# PATHS_1_1.net
KiCad netlist of a schematic drawn in EAGLE
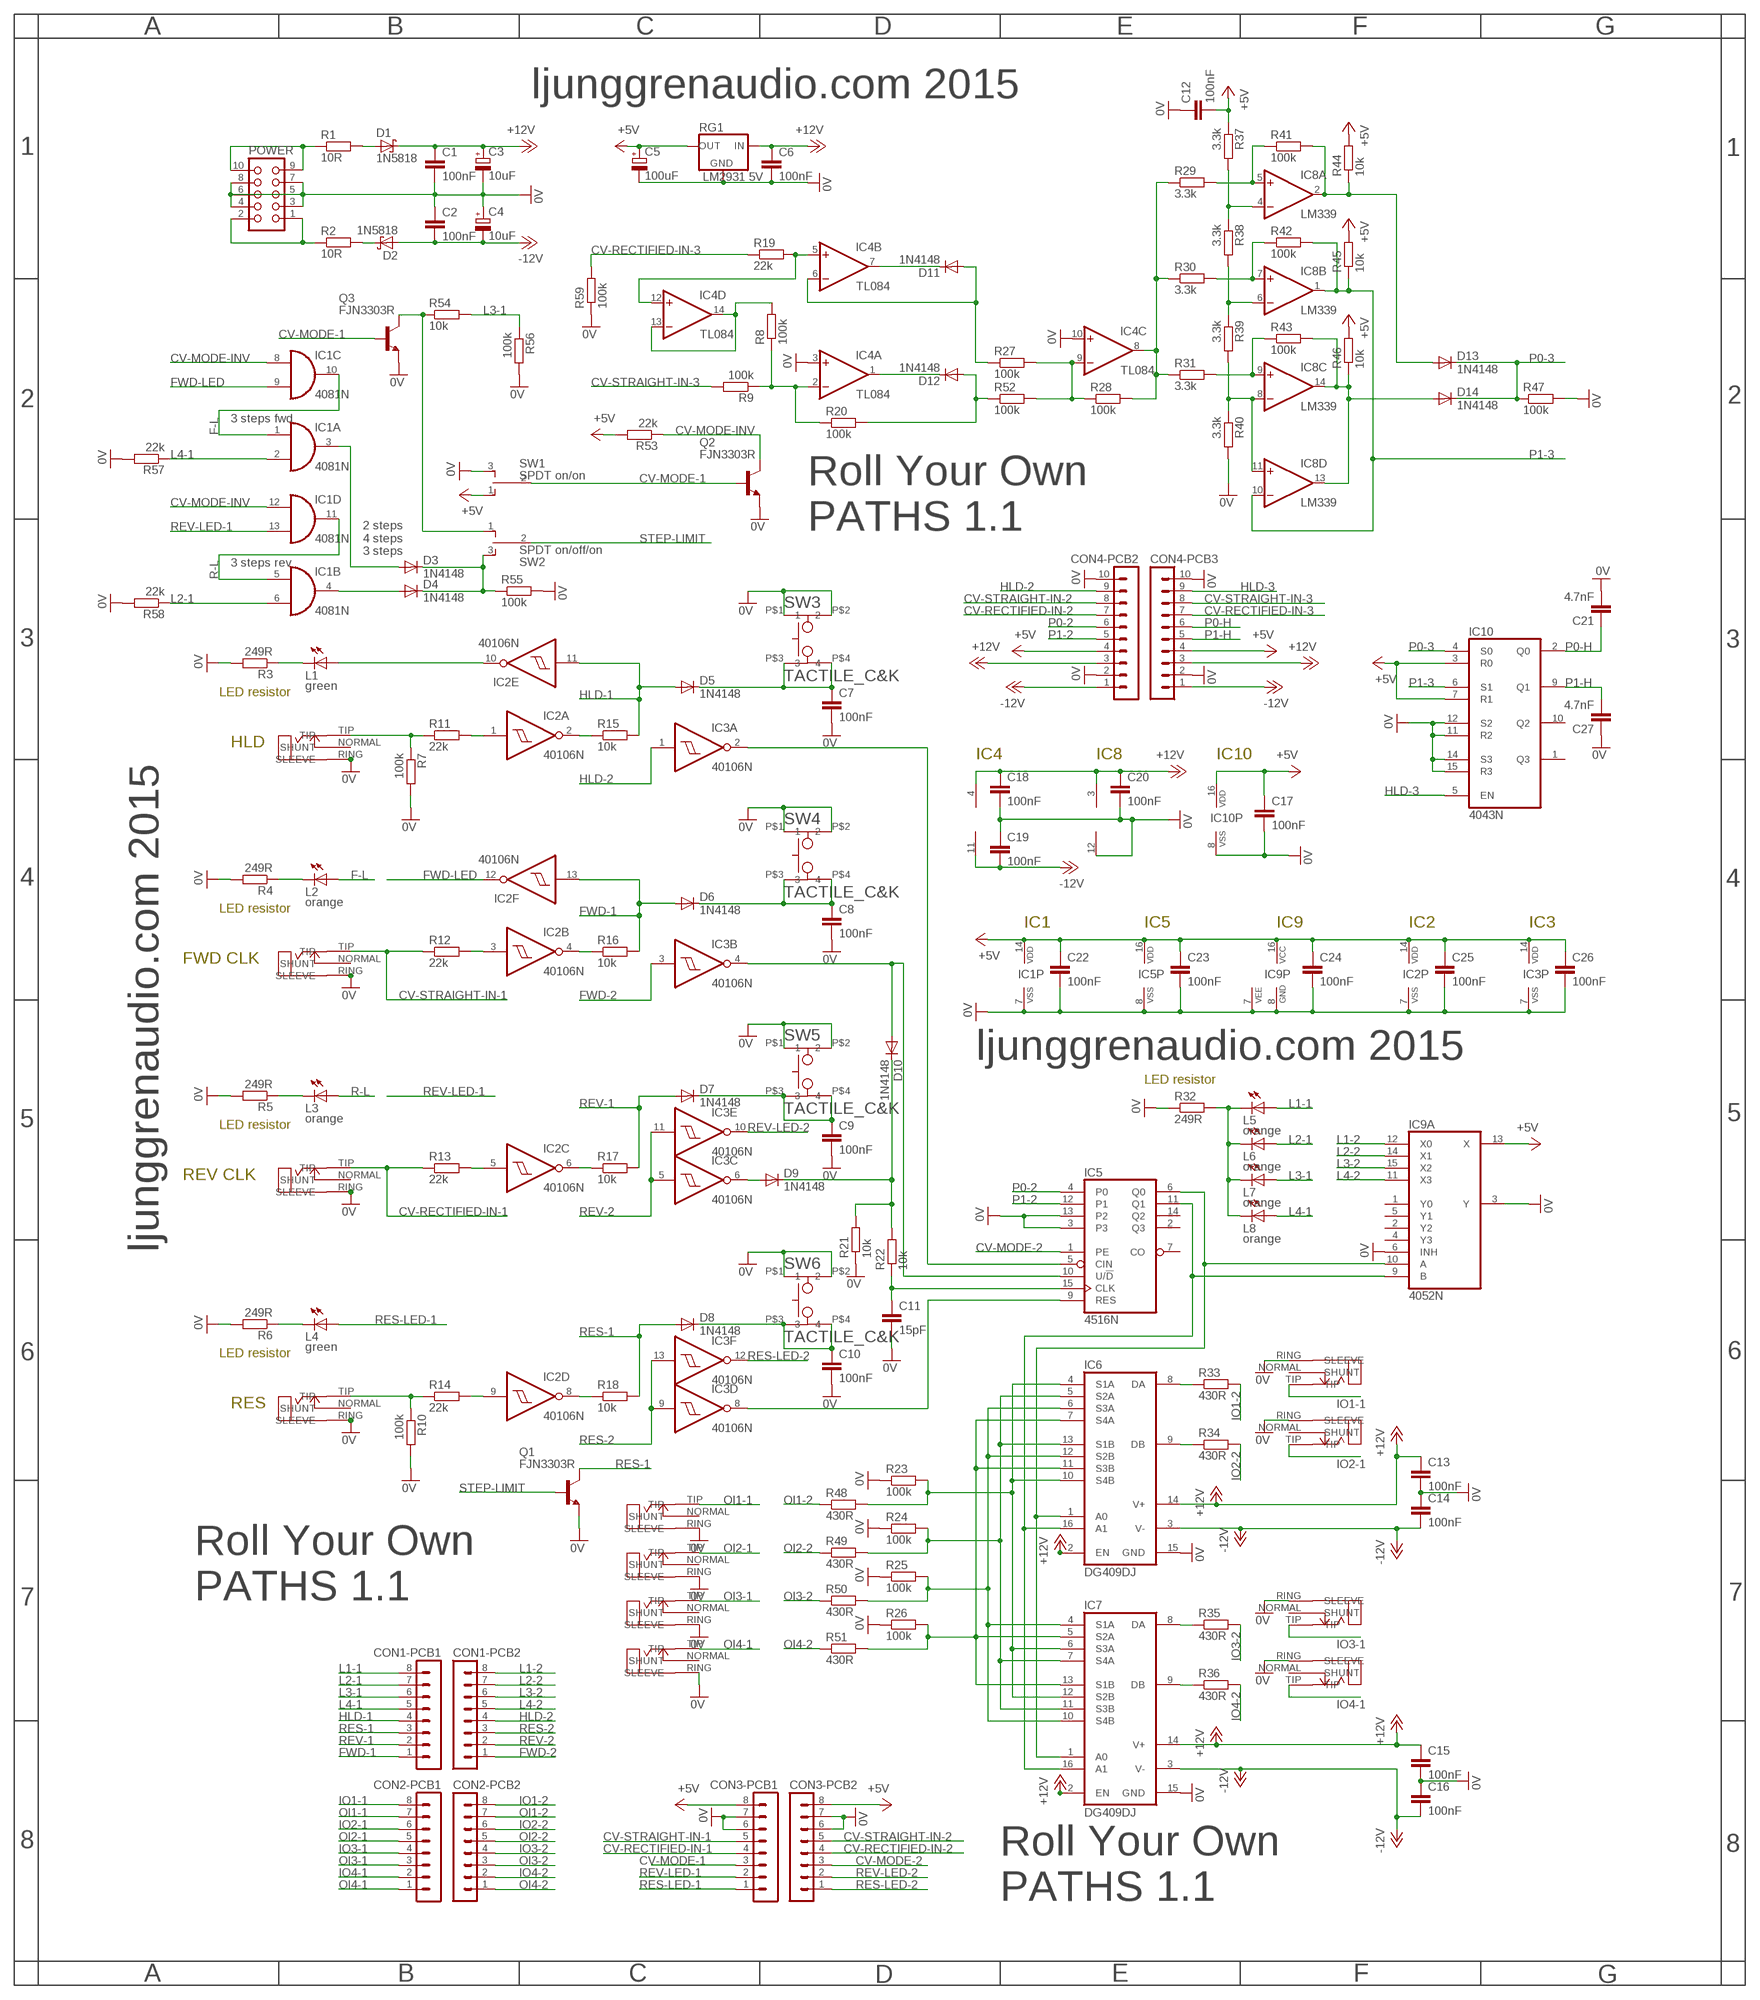
[diagram p0: schematic, sheet 1]

(export (version "E")
  (design (tool "Eeschema 10.0.6"))
  (components
    (comp (ref "C1")
      (value "100nF")
      (footprint "eagle-import:C025-024X044")
      (libsource (lib "eagle-import") (part "C-EU025-024X044"))
    )
    (comp (ref "C2")
      (value "100nF")
      (footprint "eagle-import:C025-024X044")
      (libsource (lib "eagle-import") (part "C-EU025-024X044"))
    )
    (comp (ref "C3")
      (value "10uF")
      (footprint "eagle-import:E2-5")
      (libsource (lib "eagle-import") (part "CPOL-EUE2-5"))
    )
    (comp (ref "C4")
      (value "10uF")
      (footprint "eagle-import:E2-5")
      (libsource (lib "eagle-import") (part "CPOL-EUE2-5"))
    )
    (comp (ref "C5")
      (value "100uF")
      (footprint "eagle-import:E2,5-6")
      (libsource (lib "eagle-import") (part "CPOL-EUE2.5-6"))
    )
    (comp (ref "C6")
      (value "100nF")
      (footprint "eagle-import:C025-024X044")
      (libsource (lib "eagle-import") (part "C-EU025-024X044"))
    )
    (comp (ref "C7")
      (value "100nF")
      (footprint "eagle-import:C025-024X044")
      (libsource (lib "eagle-import") (part "C-EU025-024X044"))
    )
    (comp (ref "C8")
      (value "100nF")
      (footprint "eagle-import:C025-024X044")
      (libsource (lib "eagle-import") (part "C-EU025-024X044"))
    )
    (comp (ref "C9")
      (value "100nF")
      (footprint "eagle-import:C025-024X044")
      (libsource (lib "eagle-import") (part "C-EU025-024X044"))
    )
    (comp (ref "C10")
      (value "100nF")
      (footprint "eagle-import:C025-024X044")
      (libsource (lib "eagle-import") (part "C-EU025-024X044"))
    )
    (comp (ref "C11")
      (value "15pF")
      (footprint "eagle-import:C025-024X044")
      (libsource (lib "eagle-import") (part "C-EU025-024X044"))
    )
    (comp (ref "C12")
      (value "100nF")
      (footprint "eagle-import:C025-024X044")
      (libsource (lib "eagle-import") (part "C-EU025-024X044"))
    )
    (comp (ref "C13")
      (value "100nF")
      (footprint "eagle-import:C025-024X044")
      (libsource (lib "eagle-import") (part "C-EU025-024X044"))
    )
    (comp (ref "C14")
      (value "100nF")
      (footprint "eagle-import:C025-024X044")
      (libsource (lib "eagle-import") (part "C-EU025-024X044"))
    )
    (comp (ref "C15")
      (value "100nF")
      (footprint "eagle-import:C025-024X044")
      (libsource (lib "eagle-import") (part "C-EU025-024X044"))
    )
    (comp (ref "C16")
      (value "100nF")
      (footprint "eagle-import:C025-024X044")
      (libsource (lib "eagle-import") (part "C-EU025-024X044"))
    )
    (comp (ref "C17")
      (value "100nF")
      (footprint "eagle-import:C025-024X044")
      (libsource (lib "eagle-import") (part "C-EU025-024X044"))
    )
    (comp (ref "C18")
      (value "100nF")
      (footprint "eagle-import:C025-024X044")
      (libsource (lib "eagle-import") (part "C-EU025-024X044"))
    )
    (comp (ref "C19")
      (value "100nF")
      (footprint "eagle-import:C025-024X044")
      (libsource (lib "eagle-import") (part "C-EU025-024X044"))
    )
    (comp (ref "C20")
      (value "100nF")
      (footprint "eagle-import:C025-024X044")
      (libsource (lib "eagle-import") (part "C-EU025-024X044"))
    )
    (comp (ref "C21")
      (value "4.7nF")
      (footprint "eagle-import:C025-024X044")
      (libsource (lib "eagle-import") (part "C-EU025-024X044"))
    )
    (comp (ref "C22")
      (value "100nF")
      (footprint "eagle-import:C025-024X044")
      (libsource (lib "eagle-import") (part "C-EU025-024X044"))
    )
    (comp (ref "C23")
      (value "100nF")
      (footprint "eagle-import:C025-024X044")
      (libsource (lib "eagle-import") (part "C-EU025-024X044"))
    )
    (comp (ref "C24")
      (value "100nF")
      (footprint "eagle-import:C025-024X044")
      (libsource (lib "eagle-import") (part "C-EU025-024X044"))
    )
    (comp (ref "C25")
      (value "100nF")
      (footprint "eagle-import:C025-024X044")
      (libsource (lib "eagle-import") (part "C-EU025-024X044"))
    )
    (comp (ref "C26")
      (value "100nF")
      (footprint "eagle-import:C025-024X044")
      (libsource (lib "eagle-import") (part "C-EU025-024X044"))
    )
    (comp (ref "C27")
      (value "4.7nF")
      (footprint "eagle-import:C025-024X044")
      (libsource (lib "eagle-import") (part "C-EU025-024X044"))
    )
    (comp (ref "CON1-PCB1")
      (value "MA08-1")
      (footprint "eagle-import:MA08-1")
      (libsource (lib "eagle-import") (part "MA08-1"))
    )
    (comp (ref "CON1-PCB2")
      (value "MA08-1")
      (footprint "eagle-import:MA08-1")
      (libsource (lib "eagle-import") (part "MA08-1"))
    )
    (comp (ref "CON2-PCB1")
      (value "MA08-1")
      (footprint "eagle-import:MA08-1")
      (libsource (lib "eagle-import") (part "MA08-1"))
    )
    (comp (ref "CON2-PCB2")
      (value "MA08-1")
      (footprint "eagle-import:MA08-1")
      (libsource (lib "eagle-import") (part "MA08-1"))
    )
    (comp (ref "CON3-PCB1")
      (value "MA08-1")
      (footprint "eagle-import:MA08-1")
      (libsource (lib "eagle-import") (part "MA08-1"))
    )
    (comp (ref "CON3-PCB2")
      (value "MA08-1")
      (footprint "eagle-import:MA08-1")
      (libsource (lib "eagle-import") (part "MA08-1"))
    )
    (comp (ref "CON4-PCB2")
      (value "MA10-1")
      (footprint "eagle-import:MA10-1")
      (libsource (lib "eagle-import") (part "MA10-1"))
    )
    (comp (ref "CON4-PCB3")
      (value "MA10-1")
      (footprint "eagle-import:MA10-1")
      (libsource (lib "eagle-import") (part "MA10-1"))
    )
    (comp (ref "D1")
      (value "1N5818")
      (footprint "eagle-import:DO41-7")
      (libsource (lib "eagle-import") (part "SB130DO-204AL"))
    )
    (comp (ref "D2")
      (value "1N5818")
      (footprint "eagle-import:DO41-7")
      (libsource (lib "eagle-import") (part "SB130DO-204AL"))
    )
    (comp (ref "D3")
      (value "1N4148")
      (footprint "eagle-import:DO35-6")
      (libsource (lib "eagle-import") (part "1N4148DO35-6"))
    )
    (comp (ref "D4")
      (value "1N4148")
      (footprint "eagle-import:DO35-6")
      (libsource (lib "eagle-import") (part "1N4148DO35-6"))
    )
    (comp (ref "D5")
      (value "1N4148")
      (footprint "eagle-import:DO35-6")
      (libsource (lib "eagle-import") (part "1N4148DO35-6"))
    )
    (comp (ref "D6")
      (value "1N4148")
      (footprint "eagle-import:DO35-6")
      (libsource (lib "eagle-import") (part "1N4148DO35-6"))
    )
    (comp (ref "D7")
      (value "1N4148")
      (footprint "eagle-import:DO35-6")
      (libsource (lib "eagle-import") (part "1N4148DO35-6"))
    )
    (comp (ref "D8")
      (value "1N4148")
      (footprint "eagle-import:DO35-6")
      (libsource (lib "eagle-import") (part "1N4148DO35-6"))
    )
    (comp (ref "D9")
      (value "1N4148")
      (footprint "eagle-import:DO35-6")
      (libsource (lib "eagle-import") (part "1N4148DO35-6"))
    )
    (comp (ref "D10")
      (value "1N4148")
      (footprint "eagle-import:DO35-6")
      (libsource (lib "eagle-import") (part "1N4148DO35-6"))
    )
    (comp (ref "D11")
      (value "1N4148")
      (footprint "eagle-import:DO35-6")
      (libsource (lib "eagle-import") (part "1N4148DO35-6"))
    )
    (comp (ref "D12")
      (value "1N4148")
      (footprint "eagle-import:DO35-6")
      (libsource (lib "eagle-import") (part "1N4148DO35-6"))
    )
    (comp (ref "D13")
      (value "1N4148")
      (footprint "eagle-import:DO35-6")
      (libsource (lib "eagle-import") (part "1N4148DO35-6"))
    )
    (comp (ref "D14")
      (value "1N4148")
      (footprint "eagle-import:DO35-6")
      (libsource (lib "eagle-import") (part "1N4148DO35-6"))
    )
    (comp (ref "FWD")
      (value "ERTHENVAR_3.5MM_JACKINLINE2")
      (footprint "eagle-import:THONKICON-TWISTED")
      (libsource (lib "eagle-import") (part "ERTHENVAR_3.5MM_JACKINLINE2"))
    )
    (comp (ref "HLD")
      (value "ERTHENVAR_3.5MM_JACKINLINE2")
      (footprint "eagle-import:THONKICON-TWISTED")
      (libsource (lib "eagle-import") (part "ERTHENVAR_3.5MM_JACKINLINE2"))
    )
    (comp (ref "I/O1")
      (value "ERTHENVAR_3.5MM_JACKINLINE2")
      (footprint "eagle-import:THONKICON-TWISTED")
      (libsource (lib "eagle-import") (part "ERTHENVAR_3.5MM_JACKINLINE2"))
    )
    (comp (ref "I/O2")
      (value "ERTHENVAR_3.5MM_JACKINLINE2")
      (footprint "eagle-import:THONKICON-TWISTED")
      (libsource (lib "eagle-import") (part "ERTHENVAR_3.5MM_JACKINLINE2"))
    )
    (comp (ref "I/O3")
      (value "ERTHENVAR_3.5MM_JACKINLINE2")
      (footprint "eagle-import:THONKICON-TWISTED")
      (libsource (lib "eagle-import") (part "ERTHENVAR_3.5MM_JACKINLINE2"))
    )
    (comp (ref "I/O4")
      (value "ERTHENVAR_3.5MM_JACKINLINE2")
      (footprint "eagle-import:THONKICON-TWISTED")
      (libsource (lib "eagle-import") (part "ERTHENVAR_3.5MM_JACKINLINE2"))
    )
    (comp (ref "IC1")
      (value "4081N")
      (footprint "eagle-import:DIL14")
      (libsource (lib "eagle-import") (part "4081N"))
    )
    (comp (ref "IC2")
      (value "40106N")
      (footprint "eagle-import:DIL14")
      (libsource (lib "eagle-import") (part "40106N"))
    )
    (comp (ref "IC3")
      (value "40106N")
      (footprint "eagle-import:DIL14")
      (libsource (lib "eagle-import") (part "40106N"))
    )
    (comp (ref "IC4")
      (value "TL084")
      (footprint "eagle-import:DIL14")
      (libsource (lib "eagle-import") (part "TL074P"))
    )
    (comp (ref "IC5")
      (value "4516N")
      (footprint "eagle-import:DIL16")
      (libsource (lib "eagle-import") (part "4516N"))
    )
    (comp (ref "IC6")
      (value "DG409DJ")
      (footprint "eagle-import:DIL16")
      (fields (field (name "MF") "INTERSIL"))
      (libsource (lib "eagle-import") (part "DG409DJ"))
    )
    (comp (ref "IC7")
      (value "DG409DJ")
      (footprint "eagle-import:DIL16")
      (fields (field (name "MF") "INTERSIL"))
      (libsource (lib "eagle-import") (part "DG409DJ"))
    )
    (comp (ref "IC8")
      (value "LM339")
      (footprint "eagle-import:DIL14")
      (libsource (lib "eagle-import") (part "LM2901N"))
    )
    (comp (ref "IC9")
      (value "4052N")
      (footprint "eagle-import:DIL16")
      (libsource (lib "eagle-import") (part "4052N"))
    )
    (comp (ref "IC10")
      (value "4043N")
      (footprint "eagle-import:DIL16")
      (libsource (lib "eagle-import") (part "4043N"))
    )
    (comp (ref "L1")
      (value "green")
      (footprint "eagle-import:LED3MM")
      (libsource (lib "eagle-import") (part "LED3MM"))
    )
    (comp (ref "L2")
      (value "orange")
      (footprint "eagle-import:LED3MM")
      (libsource (lib "eagle-import") (part "LED3MM"))
    )
    (comp (ref "L3")
      (value "orange")
      (footprint "eagle-import:LED3MM")
      (libsource (lib "eagle-import") (part "LED3MM"))
    )
    (comp (ref "L4")
      (value "green")
      (footprint "eagle-import:LED3MM")
      (libsource (lib "eagle-import") (part "LED3MM"))
    )
    (comp (ref "L5")
      (value "orange")
      (footprint "eagle-import:LED3MM")
      (libsource (lib "eagle-import") (part "LED3MM"))
    )
    (comp (ref "L6")
      (value "orange")
      (footprint "eagle-import:LED3MM")
      (libsource (lib "eagle-import") (part "LED3MM"))
    )
    (comp (ref "L7")
      (value "orange")
      (footprint "eagle-import:LED3MM")
      (libsource (lib "eagle-import") (part "LED3MM"))
    )
    (comp (ref "L8")
      (value "orange")
      (footprint "eagle-import:LED3MM")
      (libsource (lib "eagle-import") (part "LED3MM"))
    )
    (comp (ref "O/I1")
      (value "ERTHENVAR_3.5MM_JACKINLINE2")
      (footprint "eagle-import:THONKICON-TWISTED")
      (libsource (lib "eagle-import") (part "ERTHENVAR_3.5MM_JACKINLINE2"))
    )
    (comp (ref "O/I2")
      (value "ERTHENVAR_3.5MM_JACKINLINE2")
      (footprint "eagle-import:THONKICON-TWISTED")
      (libsource (lib "eagle-import") (part "ERTHENVAR_3.5MM_JACKINLINE2"))
    )
    (comp (ref "O/I3")
      (value "ERTHENVAR_3.5MM_JACKINLINE2")
      (footprint "eagle-import:THONKICON-TWISTED")
      (libsource (lib "eagle-import") (part "ERTHENVAR_3.5MM_JACKINLINE2"))
    )
    (comp (ref "O/I4")
      (value "ERTHENVAR_3.5MM_JACKINLINE2")
      (footprint "eagle-import:THONKICON-TWISTED")
      (libsource (lib "eagle-import") (part "ERTHENVAR_3.5MM_JACKINLINE2"))
    )
    (comp (ref "POWER")
      (value "CON10L")
      (footprint "eagle-import:CON10L")
      (libsource (lib "eagle-import") (part "CON10L"))
    )
    (comp (ref "Q1")
      (value "FJN3303R")
      (footprint "eagle-import:TO92-LINE")
      (libsource (lib "eagle-import") (part "FJN3303R"))
    )
    (comp (ref "Q2")
      (value "FJN3303R")
      (footprint "eagle-import:TO92-LINE")
      (libsource (lib "eagle-import") (part "FJN3303R"))
    )
    (comp (ref "Q3")
      (value "FJN3303R")
      (footprint "eagle-import:TO92-LINE")
      (libsource (lib "eagle-import") (part "FJN3303R"))
    )
    (comp (ref "R1")
      (value "10R")
      (footprint "eagle-import:0207_9")
      (libsource (lib "eagle-import") (part "R-EU_0207/10"))
    )
    (comp (ref "R2")
      (value "10R")
      (footprint "eagle-import:0207_9")
      (libsource (lib "eagle-import") (part "R-EU_0207/10"))
    )
    (comp (ref "R3")
      (value "249R")
      (footprint "eagle-import:0204_5")
      (libsource (lib "eagle-import") (part "R-EU_0204/5"))
    )
    (comp (ref "R4")
      (value "249R")
      (footprint "eagle-import:0204_5")
      (libsource (lib "eagle-import") (part "R-EU_0204/5"))
    )
    (comp (ref "R5")
      (value "249R")
      (footprint "eagle-import:0204_5")
      (libsource (lib "eagle-import") (part "R-EU_0204/5"))
    )
    (comp (ref "R6")
      (value "249R")
      (footprint "eagle-import:0204_5")
      (libsource (lib "eagle-import") (part "R-EU_0204/5"))
    )
    (comp (ref "R7")
      (value "100k")
      (footprint "eagle-import:0204_5")
      (libsource (lib "eagle-import") (part "R-EU_0204/5"))
    )
    (comp (ref "R8")
      (value "100k")
      (footprint "eagle-import:0204_5")
      (libsource (lib "eagle-import") (part "R-EU_0204/5"))
    )
    (comp (ref "R9")
      (value "100k")
      (footprint "eagle-import:0204_5")
      (libsource (lib "eagle-import") (part "R-EU_0204/5"))
    )
    (comp (ref "R10")
      (value "100k")
      (footprint "eagle-import:0204_5")
      (libsource (lib "eagle-import") (part "R-EU_0204/5"))
    )
    (comp (ref "R11")
      (value "22k")
      (footprint "eagle-import:0204_5")
      (libsource (lib "eagle-import") (part "R-EU_0204/5"))
    )
    (comp (ref "R12")
      (value "22k")
      (footprint "eagle-import:0204_5")
      (libsource (lib "eagle-import") (part "R-EU_0204/5"))
    )
    (comp (ref "R13")
      (value "22k")
      (footprint "eagle-import:0204_5")
      (libsource (lib "eagle-import") (part "R-EU_0204/5"))
    )
    (comp (ref "R14")
      (value "22k")
      (footprint "eagle-import:0204_5")
      (libsource (lib "eagle-import") (part "R-EU_0204/5"))
    )
    (comp (ref "R15")
      (value "10k")
      (footprint "eagle-import:0204_5")
      (libsource (lib "eagle-import") (part "R-EU_0204/5"))
    )
    (comp (ref "R16")
      (value "10k")
      (footprint "eagle-import:0204_5")
      (libsource (lib "eagle-import") (part "R-EU_0204/5"))
    )
    (comp (ref "R17")
      (value "10k")
      (footprint "eagle-import:0204_5")
      (libsource (lib "eagle-import") (part "R-EU_0204/5"))
    )
    (comp (ref "R18")
      (value "10k")
      (footprint "eagle-import:0204_5")
      (libsource (lib "eagle-import") (part "R-EU_0204/5"))
    )
    (comp (ref "R19")
      (value "22k")
      (footprint "eagle-import:0204_5")
      (libsource (lib "eagle-import") (part "R-EU_0204/5"))
    )
    (comp (ref "R20")
      (value "100k")
      (footprint "eagle-import:0204_5")
      (libsource (lib "eagle-import") (part "R-EU_0204/5"))
    )
    (comp (ref "R21")
      (value "10k")
      (footprint "eagle-import:0204_5")
      (libsource (lib "eagle-import") (part "R-EU_0204/5"))
    )
    (comp (ref "R22")
      (value "10k")
      (footprint "eagle-import:0204_5")
      (libsource (lib "eagle-import") (part "R-EU_0204/5"))
    )
    (comp (ref "R23")
      (value "100k")
      (footprint "eagle-import:0204_5")
      (libsource (lib "eagle-import") (part "R-EU_0204/5"))
    )
    (comp (ref "R24")
      (value "100k")
      (footprint "eagle-import:0204_5")
      (libsource (lib "eagle-import") (part "R-EU_0204/5"))
    )
    (comp (ref "R25")
      (value "100k")
      (footprint "eagle-import:0204_5")
      (libsource (lib "eagle-import") (part "R-EU_0204/5"))
    )
    (comp (ref "R26")
      (value "100k")
      (footprint "eagle-import:0204_5")
      (libsource (lib "eagle-import") (part "R-EU_0204/5"))
    )
    (comp (ref "R27")
      (value "100k")
      (footprint "eagle-import:0204_5")
      (libsource (lib "eagle-import") (part "R-EU_0204/5"))
    )
    (comp (ref "R28")
      (value "100k")
      (footprint "eagle-import:0204_5")
      (libsource (lib "eagle-import") (part "R-EU_0204/5"))
    )
    (comp (ref "R29")
      (value "3.3k")
      (footprint "eagle-import:0204_5")
      (libsource (lib "eagle-import") (part "R-EU_0204/5"))
    )
    (comp (ref "R30")
      (value "3.3k")
      (footprint "eagle-import:0204_5")
      (libsource (lib "eagle-import") (part "R-EU_0204/5"))
    )
    (comp (ref "R31")
      (value "3.3k")
      (footprint "eagle-import:0204_5")
      (libsource (lib "eagle-import") (part "R-EU_0204/5"))
    )
    (comp (ref "R32")
      (value "249R")
      (footprint "eagle-import:0204_5")
      (libsource (lib "eagle-import") (part "R-EU_0204/5"))
    )
    (comp (ref "R33")
      (value "430R")
      (footprint "eagle-import:0207_9")
      (libsource (lib "eagle-import") (part "R-EU_0207/10"))
    )
    (comp (ref "R34")
      (value "430R")
      (footprint "eagle-import:0207_9")
      (libsource (lib "eagle-import") (part "R-EU_0207/10"))
    )
    (comp (ref "R35")
      (value "430R")
      (footprint "eagle-import:0207_9")
      (libsource (lib "eagle-import") (part "R-EU_0207/10"))
    )
    (comp (ref "R36")
      (value "430R")
      (footprint "eagle-import:0207_9")
      (libsource (lib "eagle-import") (part "R-EU_0207/10"))
    )
    (comp (ref "R37")
      (value "3.3k")
      (footprint "eagle-import:0204_5")
      (libsource (lib "eagle-import") (part "R-EU_0204/5"))
    )
    (comp (ref "R38")
      (value "3.3k")
      (footprint "eagle-import:0204_5")
      (libsource (lib "eagle-import") (part "R-EU_0204/5"))
    )
    (comp (ref "R39")
      (value "3.3k")
      (footprint "eagle-import:0204_5")
      (libsource (lib "eagle-import") (part "R-EU_0204/5"))
    )
    (comp (ref "R40")
      (value "3.3k")
      (footprint "eagle-import:0204_5")
      (libsource (lib "eagle-import") (part "R-EU_0204/5"))
    )
    (comp (ref "R41")
      (value "100k")
      (footprint "eagle-import:0204_5")
      (libsource (lib "eagle-import") (part "R-EU_0204/5"))
    )
    (comp (ref "R42")
      (value "100k")
      (footprint "eagle-import:0204_5")
      (libsource (lib "eagle-import") (part "R-EU_0204/5"))
    )
    (comp (ref "R43")
      (value "100k")
      (footprint "eagle-import:0204_5")
      (libsource (lib "eagle-import") (part "R-EU_0204/5"))
    )
    (comp (ref "R44")
      (value "10k")
      (footprint "eagle-import:0204_5")
      (libsource (lib "eagle-import") (part "R-EU_0204/5"))
    )
    (comp (ref "R45")
      (value "10k")
      (footprint "eagle-import:0204_5")
      (libsource (lib "eagle-import") (part "R-EU_0204/5"))
    )
    (comp (ref "R46")
      (value "10k")
      (footprint "eagle-import:0204_5")
      (libsource (lib "eagle-import") (part "R-EU_0204/5"))
    )
    (comp (ref "R47")
      (value "100k")
      (footprint "eagle-import:0204_5")
      (libsource (lib "eagle-import") (part "R-EU_0204/5"))
    )
    (comp (ref "R48")
      (value "430R")
      (footprint "eagle-import:0207_9")
      (libsource (lib "eagle-import") (part "R-EU_0207/10"))
    )
    (comp (ref "R49")
      (value "430R")
      (footprint "eagle-import:0207_9")
      (libsource (lib "eagle-import") (part "R-EU_0207/10"))
    )
    (comp (ref "R50")
      (value "430R")
      (footprint "eagle-import:0207_9")
      (libsource (lib "eagle-import") (part "R-EU_0207/10"))
    )
    (comp (ref "R51")
      (value "430R")
      (footprint "eagle-import:0207_9")
      (libsource (lib "eagle-import") (part "R-EU_0207/10"))
    )
    (comp (ref "R52")
      (value "100k")
      (footprint "eagle-import:0204_5")
      (libsource (lib "eagle-import") (part "R-EU_0204/5"))
    )
    (comp (ref "R53")
      (value "22k")
      (footprint "eagle-import:0204_5")
      (libsource (lib "eagle-import") (part "R-EU_0204/5"))
    )
    (comp (ref "R54")
      (value "10k")
      (footprint "eagle-import:0204_5")
      (libsource (lib "eagle-import") (part "R-EU_0204/5"))
    )
    (comp (ref "R55")
      (value "100k")
      (footprint "eagle-import:0204_5")
      (libsource (lib "eagle-import") (part "R-EU_0204/5"))
    )
    (comp (ref "R56")
      (value "100k")
      (footprint "eagle-import:0204_5")
      (libsource (lib "eagle-import") (part "R-EU_0204/5"))
    )
    (comp (ref "R57")
      (value "22k")
      (footprint "eagle-import:0204_5")
      (libsource (lib "eagle-import") (part "R-EU_0204/5"))
    )
    (comp (ref "R58")
      (value "22k")
      (footprint "eagle-import:0204_5")
      (libsource (lib "eagle-import") (part "R-EU_0204/5"))
    )
    (comp (ref "R59")
      (value "100k")
      (footprint "eagle-import:0204_5")
      (libsource (lib "eagle-import") (part "R-EU_0204/5"))
    )
    (comp (ref "RES")
      (value "ERTHENVAR_3.5MM_JACKINLINE2")
      (footprint "eagle-import:THONKICON-TWISTED")
      (libsource (lib "eagle-import") (part "ERTHENVAR_3.5MM_JACKINLINE2"))
    )
    (comp (ref "REV")
      (value "ERTHENVAR_3.5MM_JACKINLINE2")
      (footprint "eagle-import:THONKICON-TWISTED")
      (libsource (lib "eagle-import") (part "ERTHENVAR_3.5MM_JACKINLINE2"))
    )
    (comp (ref "RG1")
      (value "LM2931 5V")
      (footprint "eagle-import:TO92-LINE")
      (libsource (lib "eagle-import") (part "78LXXLM2931XXX"))
    )
    (comp (ref "SW1")
      (value "SPDT on/on")
      (footprint "eagle-import:SPDT-HORIZONTAL-TOP-SUBMINI-MULTICOMP")
      (libsource (lib "eagle-import") (part "SPDTTOP-SUBMINI"))
    )
    (comp (ref "SW2")
      (value "SPDT on/off/on")
      (footprint "eagle-import:SPDT-HORIZONTAL-TOP-SUBMINI-MULTICOMP")
      (libsource (lib "eagle-import") (part "SPDTTOP-SUBMINI"))
    )
    (comp (ref "SW3")
      (value "TACTILE_C&K")
      (footprint "eagle-import:TACTILE_CK")
      (libsource (lib "eagle-import") (part "TACTILE_C&K"))
    )
    (comp (ref "SW4")
      (value "TACTILE_C&K")
      (footprint "eagle-import:TACTILE_CK")
      (libsource (lib "eagle-import") (part "TACTILE_C&K"))
    )
    (comp (ref "SW5")
      (value "TACTILE_C&K")
      (footprint "eagle-import:TACTILE_CK")
      (libsource (lib "eagle-import") (part "TACTILE_C&K"))
    )
    (comp (ref "SW6")
      (value "TACTILE_C&K")
      (footprint "eagle-import:TACTILE_CK")
      (libsource (lib "eagle-import") (part "TACTILE_C&K"))
    )
  )
  (nets
    (net (code "1") (name "+5V") (class "Default")
      (node (ref "C12") (pin "2") (pinfunction "2_2") (pintype "passive"))
      (node (ref "C17") (pin "1") (pinfunction "1_1") (pintype "passive"))
      (node (ref "C22") (pin "1") (pinfunction "1_1") (pintype "passive"))
      (node (ref "C23") (pin "1") (pinfunction "1_1") (pintype "passive"))
      (node (ref "C24") (pin "1") (pinfunction "1_1") (pintype "passive"))
      (node (ref "C25") (pin "1") (pinfunction "1_1") (pintype "passive"))
      (node (ref "C26") (pin "1") (pinfunction "1_1") (pintype "passive"))
      (node (ref "C5") (pin "+") (pinfunction "+_+") (pintype "passive"))
      (node (ref "CON3-PCB1") (pin "8") (pinfunction "8_8") (pintype "passive"))
      (node (ref "CON3-PCB2") (pin "8") (pinfunction "8_8") (pintype "passive"))
      (node (ref "CON4-PCB2") (pin "4") (pinfunction "4_4") (pintype "passive"))
      (node (ref "CON4-PCB3") (pin "4") (pinfunction "4_4") (pintype "passive"))
      (node (ref "IC1") (pin "14") (pinfunction "VDD_14") (pintype "power_in"))
      (node (ref "IC10") (pin "16") (pinfunction "VDD_16") (pintype "power_in"))
      (node (ref "IC10") (pin "3") (pinfunction "R0_3") (pintype "input"))
      (node (ref "IC10") (pin "7") (pinfunction "R1_7") (pintype "input"))
      (node (ref "IC2") (pin "14") (pinfunction "VDD_14") (pintype "power_in"))
      (node (ref "IC3") (pin "14") (pinfunction "VDD_14") (pintype "power_in"))
      (node (ref "IC5") (pin "16") (pinfunction "VDD_16") (pintype "power_in"))
      (node (ref "IC9") (pin "13") (pinfunction "X_13") (pintype "bidirectional"))
      (node (ref "IC9") (pin "16") (pinfunction "VCC_16") (pintype "power_in"))
      (node (ref "R37") (pin "1") (pinfunction "1_1") (pintype "passive"))
      (node (ref "R44") (pin "2") (pinfunction "2_2") (pintype "passive"))
      (node (ref "R45") (pin "2") (pinfunction "2_2") (pintype "passive"))
      (node (ref "R46") (pin "2") (pinfunction "2_2") (pintype "passive"))
      (node (ref "R53") (pin "2") (pinfunction "2_2") (pintype "passive"))
      (node (ref "RG1") (pin "3") (pinfunction "OUT_3") (pintype "passive"))
      (node (ref "SW1") (pin "1") (pinfunction "1_1") (pintype "passive"))
    )
    (net (code "2") (name "+12V") (class "Default")
      (node (ref "C1") (pin "1") (pinfunction "1_1") (pintype "passive"))
      (node (ref "C13") (pin "1") (pinfunction "1_1") (pintype "passive"))
      (node (ref "C15") (pin "1") (pinfunction "1_1") (pintype "passive"))
      (node (ref "C18") (pin "1") (pinfunction "1_1") (pintype "passive"))
      (node (ref "C20") (pin "1") (pinfunction "1_1") (pintype "passive"))
      (node (ref "C3") (pin "+") (pinfunction "+_+") (pintype "passive"))
      (node (ref "C6") (pin "1") (pinfunction "1_1") (pintype "passive"))
      (node (ref "CON4-PCB2") (pin "3") (pinfunction "3_3") (pintype "passive"))
      (node (ref "CON4-PCB3") (pin "3") (pinfunction "3_3") (pintype "passive"))
      (node (ref "D1") (pin "C") (pinfunction "C_C") (pintype "passive"))
      (node (ref "IC4") (pin "4") (pinfunction "V+_4") (pintype "power_in"))
      (node (ref "IC6") (pin "14") (pinfunction "V+_14") (pintype "power_in"))
      (node (ref "IC6") (pin "2") (pinfunction "EN_2") (pintype "input"))
      (node (ref "IC7") (pin "14") (pinfunction "V+_14") (pintype "power_in"))
      (node (ref "IC7") (pin "2") (pinfunction "EN_2") (pintype "input"))
      (node (ref "IC8") (pin "3") (pinfunction "V+_3") (pintype "power_in"))
      (node (ref "RG1") (pin "1") (pinfunction "IN_1") (pintype "input"))
    )
    (net (code "3") (name "-12V") (class "Default")
      (node (ref "C14") (pin "2") (pinfunction "2_2") (pintype "passive"))
      (node (ref "C16") (pin "2") (pinfunction "2_2") (pintype "passive"))
      (node (ref "C19") (pin "2") (pinfunction "2_2") (pintype "passive"))
      (node (ref "C2") (pin "2") (pinfunction "2_2") (pintype "passive"))
      (node (ref "C4") (pin "-") (pinfunction "-_-") (pintype "passive"))
      (node (ref "CON4-PCB2") (pin "1") (pinfunction "1_1") (pintype "passive"))
      (node (ref "CON4-PCB3") (pin "1") (pinfunction "1_1") (pintype "passive"))
      (node (ref "D2") (pin "A") (pinfunction "A_A") (pintype "passive"))
      (node (ref "IC4") (pin "11") (pinfunction "V-_11") (pintype "power_in"))
      (node (ref "IC6") (pin "3") (pinfunction "V-_3") (pintype "power_in"))
      (node (ref "IC7") (pin "3") (pinfunction "V-_3") (pintype "power_in"))
    )
    (net (code "4") (name "/CV-MODE-1") (class "Default")
      (node (ref "CON3-PCB1") (pin "3") (pinfunction "3_3") (pintype "passive"))
      (node (ref "Q2") (pin "1") (pinfunction "B_1") (pintype "passive"))
      (node (ref "Q3") (pin "1") (pinfunction "B_1") (pintype "passive"))
      (node (ref "SW1") (pin "2") (pinfunction "2_2") (pintype "passive"))
    )
    (net (code "5") (name "/CV-MODE-2") (class "Default")
      (node (ref "CON3-PCB2") (pin "3") (pinfunction "3_3") (pintype "passive"))
      (node (ref "IC5") (pin "1") (pinfunction "PE_1") (pintype "input"))
    )
    (net (code "6") (name "/CV-MODE-INV") (class "Default")
      (node (ref "IC1") (pin "12") (pinfunction "I0_12") (pintype "input"))
      (node (ref "IC1") (pin "8") (pinfunction "I0_8") (pintype "input"))
      (node (ref "Q2") (pin "2") (pinfunction "C_2") (pintype "passive"))
      (node (ref "R53") (pin "1") (pinfunction "1_1") (pintype "passive"))
    )
    (net (code "7") (name "/CV-RECTIFIED-IN-1") (class "Default")
      (node (ref "CON3-PCB1") (pin "4") (pinfunction "4_4") (pintype "passive"))
      (node (ref "R13") (pin "1") (pinfunction "1_1") (pintype "passive"))
      (node (ref "REV") (pin "TIP") (pinfunction "TIP_TIP") (pintype "bidirectional"))
    )
    (net (code "8") (name "/CV-RECTIFIED-IN-2") (class "Default")
      (node (ref "CON3-PCB2") (pin "4") (pinfunction "4_4") (pintype "passive"))
      (node (ref "CON4-PCB2") (pin "7") (pinfunction "7_7") (pintype "passive"))
    )
    (net (code "9") (name "/CV-RECTIFIED-IN-3") (class "Default")
      (node (ref "CON4-PCB3") (pin "7") (pinfunction "7_7") (pintype "passive"))
      (node (ref "R19") (pin "1") (pinfunction "1_1") (pintype "passive"))
      (node (ref "R59") (pin "2") (pinfunction "2_2") (pintype "passive"))
    )
    (net (code "10") (name "/CV-STRAIGHT-IN-1") (class "Default")
      (node (ref "CON3-PCB1") (pin "5") (pinfunction "5_5") (pintype "passive"))
      (node (ref "FWD") (pin "TIP") (pinfunction "TIP_TIP") (pintype "bidirectional"))
      (node (ref "R12") (pin "1") (pinfunction "1_1") (pintype "passive"))
    )
    (net (code "11") (name "/CV-STRAIGHT-IN-2") (class "Default")
      (node (ref "CON3-PCB2") (pin "5") (pinfunction "5_5") (pintype "passive"))
      (node (ref "CON4-PCB2") (pin "8") (pinfunction "8_8") (pintype "passive"))
    )
    (net (code "12") (name "/CV-STRAIGHT-IN-3") (class "Default")
      (node (ref "CON4-PCB3") (pin "8") (pinfunction "8_8") (pintype "passive"))
      (node (ref "R9") (pin "2") (pinfunction "2_2") (pintype "passive"))
    )
    (net (code "13") (name "/F-L") (class "Default")
      (node (ref "IC1") (pin "1") (pinfunction "I0_1") (pintype "input"))
      (node (ref "IC1") (pin "10") (pinfunction "O_10") (pintype "output"))
      (node (ref "L2") (pin "A") (pinfunction "A_A") (pintype "passive"))
    )
    (net (code "14") (name "/FWD-1") (class "Default")
      (node (ref "CON1-PCB1") (pin "1") (pinfunction "1_1") (pintype "passive"))
      (node (ref "D6") (pin "ANODE") (pinfunction "A_ANODE") (pintype "passive"))
      (node (ref "IC2") (pin "13") (pinfunction "I_13") (pintype "input"))
      (node (ref "R16") (pin "2") (pinfunction "2_2") (pintype "passive"))
    )
    (net (code "15") (name "/FWD-2") (class "Default")
      (node (ref "CON1-PCB2") (pin "1") (pinfunction "1_1") (pintype "passive"))
      (node (ref "IC3") (pin "3") (pinfunction "I_3") (pintype "input"))
    )
    (net (code "16") (name "/FWD-LED") (class "Default")
      (node (ref "IC1") (pin "9") (pinfunction "I1_9") (pintype "input"))
      (node (ref "IC2") (pin "12") (pinfunction "O_12") (pintype "output"))
    )
    (net (code "17") (name "/HLD-1") (class "Default")
      (node (ref "CON1-PCB1") (pin "4") (pinfunction "4_4") (pintype "passive"))
      (node (ref "D5") (pin "ANODE") (pinfunction "A_ANODE") (pintype "passive"))
      (node (ref "IC2") (pin "11") (pinfunction "I_11") (pintype "input"))
      (node (ref "R15") (pin "2") (pinfunction "2_2") (pintype "passive"))
    )
    (net (code "18") (name "/HLD-2") (class "Default")
      (node (ref "CON1-PCB2") (pin "4") (pinfunction "4_4") (pintype "passive"))
      (node (ref "CON4-PCB2") (pin "9") (pinfunction "9_9") (pintype "passive"))
      (node (ref "IC3") (pin "1") (pinfunction "I_1") (pintype "input"))
    )
    (net (code "19") (name "/HLD-3") (class "Default")
      (node (ref "CON4-PCB3") (pin "9") (pinfunction "9_9") (pintype "passive"))
      (node (ref "IC10") (pin "5") (pinfunction "EN_5") (pintype "input"))
    )
    (net (code "20") (name "/IO1-1") (class "Default")
      (node (ref "CON2-PCB1") (pin "8") (pinfunction "8_8") (pintype "passive"))
      (node (ref "I/O1") (pin "TIP") (pinfunction "TIP_TIP") (pintype "bidirectional"))
    )
    (net (code "21") (name "/IO1-2") (class "Default")
      (node (ref "CON2-PCB2") (pin "8") (pinfunction "8_8") (pintype "passive"))
      (node (ref "R33") (pin "2") (pinfunction "2_2") (pintype "passive"))
    )
    (net (code "22") (name "/IO2-1") (class "Default")
      (node (ref "CON2-PCB1") (pin "6") (pinfunction "6_6") (pintype "passive"))
      (node (ref "I/O2") (pin "TIP") (pinfunction "TIP_TIP") (pintype "bidirectional"))
    )
    (net (code "23") (name "/IO2-2") (class "Default")
      (node (ref "CON2-PCB2") (pin "6") (pinfunction "6_6") (pintype "passive"))
      (node (ref "R34") (pin "2") (pinfunction "2_2") (pintype "passive"))
    )
    (net (code "24") (name "/IO3-1") (class "Default")
      (node (ref "CON2-PCB1") (pin "4") (pinfunction "4_4") (pintype "passive"))
      (node (ref "I/O3") (pin "TIP") (pinfunction "TIP_TIP") (pintype "bidirectional"))
    )
    (net (code "25") (name "/IO3-2") (class "Default")
      (node (ref "CON2-PCB2") (pin "4") (pinfunction "4_4") (pintype "passive"))
      (node (ref "R35") (pin "2") (pinfunction "2_2") (pintype "passive"))
    )
    (net (code "26") (name "/IO4-1") (class "Default")
      (node (ref "CON2-PCB1") (pin "2") (pinfunction "2_2") (pintype "passive"))
      (node (ref "I/O4") (pin "TIP") (pinfunction "TIP_TIP") (pintype "bidirectional"))
    )
    (net (code "27") (name "/IO4-2") (class "Default")
      (node (ref "CON2-PCB2") (pin "2") (pinfunction "2_2") (pintype "passive"))
      (node (ref "R36") (pin "2") (pinfunction "2_2") (pintype "passive"))
    )
    (net (code "28") (name "/L1-1") (class "Default")
      (node (ref "CON1-PCB1") (pin "8") (pinfunction "8_8") (pintype "passive"))
      (node (ref "L5") (pin "A") (pinfunction "A_A") (pintype "passive"))
    )
    (net (code "29") (name "/L1-2") (class "Default")
      (node (ref "CON1-PCB2") (pin "8") (pinfunction "8_8") (pintype "passive"))
      (node (ref "IC9") (pin "12") (pinfunction "X0_12") (pintype "bidirectional"))
    )
    (net (code "30") (name "/L2-1") (class "Default")
      (node (ref "CON1-PCB1") (pin "7") (pinfunction "7_7") (pintype "passive"))
      (node (ref "IC1") (pin "6") (pinfunction "I1_6") (pintype "input"))
      (node (ref "L6") (pin "A") (pinfunction "A_A") (pintype "passive"))
      (node (ref "R58") (pin "1") (pinfunction "1_1") (pintype "passive"))
    )
    (net (code "31") (name "/L2-2") (class "Default")
      (node (ref "CON1-PCB2") (pin "7") (pinfunction "7_7") (pintype "passive"))
      (node (ref "IC9") (pin "14") (pinfunction "X1_14") (pintype "bidirectional"))
    )
    (net (code "32") (name "/L3-1") (class "Default")
      (node (ref "CON1-PCB1") (pin "6") (pinfunction "6_6") (pintype "passive"))
      (node (ref "L7") (pin "A") (pinfunction "A_A") (pintype "passive"))
      (node (ref "R54") (pin "2") (pinfunction "2_2") (pintype "passive"))
      (node (ref "R56") (pin "1") (pinfunction "1_1") (pintype "passive"))
    )
    (net (code "33") (name "/L3-2") (class "Default")
      (node (ref "CON1-PCB2") (pin "6") (pinfunction "6_6") (pintype "passive"))
      (node (ref "IC9") (pin "15") (pinfunction "X2_15") (pintype "bidirectional"))
    )
    (net (code "34") (name "/L4-1") (class "Default")
      (node (ref "CON1-PCB1") (pin "5") (pinfunction "5_5") (pintype "passive"))
      (node (ref "IC1") (pin "2") (pinfunction "I1_2") (pintype "input"))
      (node (ref "L8") (pin "A") (pinfunction "A_A") (pintype "passive"))
      (node (ref "R57") (pin "1") (pinfunction "1_1") (pintype "passive"))
    )
    (net (code "35") (name "/L4-2") (class "Default")
      (node (ref "CON1-PCB2") (pin "5") (pinfunction "5_5") (pintype "passive"))
      (node (ref "IC9") (pin "11") (pinfunction "X3_11") (pintype "bidirectional"))
    )
    (net (code "36") (name "/OI1-1") (class "Default")
      (node (ref "CON2-PCB1") (pin "7") (pinfunction "7_7") (pintype "passive"))
      (node (ref "O/I1") (pin "TIP") (pinfunction "TIP_TIP") (pintype "bidirectional"))
    )
    (net (code "37") (name "/OI1-2") (class "Default")
      (node (ref "CON2-PCB2") (pin "7") (pinfunction "7_7") (pintype "passive"))
      (node (ref "R48") (pin "1") (pinfunction "1_1") (pintype "passive"))
    )
    (net (code "38") (name "/OI2-1") (class "Default")
      (node (ref "CON2-PCB1") (pin "5") (pinfunction "5_5") (pintype "passive"))
      (node (ref "O/I2") (pin "TIP") (pinfunction "TIP_TIP") (pintype "bidirectional"))
    )
    (net (code "39") (name "/OI2-2") (class "Default")
      (node (ref "CON2-PCB2") (pin "5") (pinfunction "5_5") (pintype "passive"))
      (node (ref "R49") (pin "1") (pinfunction "1_1") (pintype "passive"))
    )
    (net (code "40") (name "/OI3-1") (class "Default")
      (node (ref "CON2-PCB1") (pin "3") (pinfunction "3_3") (pintype "passive"))
      (node (ref "O/I3") (pin "TIP") (pinfunction "TIP_TIP") (pintype "bidirectional"))
    )
    (net (code "41") (name "/OI3-2") (class "Default")
      (node (ref "CON2-PCB2") (pin "3") (pinfunction "3_3") (pintype "passive"))
      (node (ref "R50") (pin "1") (pinfunction "1_1") (pintype "passive"))
    )
    (net (code "42") (name "/OI4-1") (class "Default")
      (node (ref "CON2-PCB1") (pin "1") (pinfunction "1_1") (pintype "passive"))
      (node (ref "O/I4") (pin "TIP") (pinfunction "TIP_TIP") (pintype "bidirectional"))
    )
    (net (code "43") (name "/OI4-2") (class "Default")
      (node (ref "CON2-PCB2") (pin "1") (pinfunction "1_1") (pintype "passive"))
      (node (ref "R51") (pin "1") (pinfunction "1_1") (pintype "passive"))
    )
    (net (code "44") (name "/P0-2") (class "Default")
      (node (ref "CON4-PCB2") (pin "6") (pinfunction "6_6") (pintype "passive"))
      (node (ref "IC5") (pin "4") (pinfunction "P0_4") (pintype "input"))
    )
    (net (code "45") (name "/P0-3") (class "Default")
      (node (ref "D13") (pin "CATHODE") (pinfunction "C_CATHODE") (pintype "passive"))
      (node (ref "D14") (pin "CATHODE") (pinfunction "C_CATHODE") (pintype "passive"))
      (node (ref "IC10") (pin "4") (pinfunction "S0_4") (pintype "input"))
      (node (ref "R47") (pin "1") (pinfunction "1_1") (pintype "passive"))
    )
    (net (code "46") (name "/P0-H") (class "Default")
      (node (ref "C21") (pin "1") (pinfunction "1_1") (pintype "passive"))
      (node (ref "CON4-PCB3") (pin "6") (pinfunction "6_6") (pintype "passive"))
      (node (ref "IC10") (pin "2") (pinfunction "Q0_2") (pintype "output"))
    )
    (net (code "47") (name "/P1-2") (class "Default")
      (node (ref "CON4-PCB2") (pin "5") (pinfunction "5_5") (pintype "passive"))
      (node (ref "IC5") (pin "12") (pinfunction "P1_12") (pintype "input"))
    )
    (net (code "48") (name "/P1-3") (class "Default")
      (node (ref "IC10") (pin "6") (pinfunction "S1_6") (pintype "input"))
      (node (ref "IC8") (pin "1") (pinfunction "OUT_1") (pintype "output"))
      (node (ref "IC8") (pin "10") (pinfunction "-IN_10") (pintype "input"))
      (node (ref "R42") (pin "2") (pinfunction "2_2") (pintype "passive"))
      (node (ref "R45") (pin "1") (pinfunction "1_1") (pintype "passive"))
    )
    (net (code "49") (name "/P1-H") (class "Default")
      (node (ref "C27") (pin "2") (pinfunction "2_2") (pintype "passive"))
      (node (ref "CON4-PCB3") (pin "5") (pinfunction "5_5") (pintype "passive"))
      (node (ref "IC10") (pin "9") (pinfunction "Q1_9") (pintype "output"))
    )
    (net (code "50") (name "/R-L") (class "Default")
      (node (ref "IC1") (pin "11") (pinfunction "O_11") (pintype "output"))
      (node (ref "IC1") (pin "5") (pinfunction "I0_5") (pintype "input"))
      (node (ref "L3") (pin "A") (pinfunction "A_A") (pintype "passive"))
    )
    (net (code "51") (name "/RES-1") (class "Default")
      (node (ref "CON1-PCB1") (pin "3") (pinfunction "3_3") (pintype "passive"))
      (node (ref "D8") (pin "ANODE") (pinfunction "A_ANODE") (pintype "passive"))
      (node (ref "Q1") (pin "2") (pinfunction "C_2") (pintype "passive"))
      (node (ref "R18") (pin "2") (pinfunction "2_2") (pintype "passive"))
    )
    (net (code "52") (name "/RES-2") (class "Default")
      (node (ref "CON1-PCB2") (pin "3") (pinfunction "3_3") (pintype "passive"))
      (node (ref "IC3") (pin "13") (pinfunction "I_13") (pintype "input"))
      (node (ref "IC3") (pin "9") (pinfunction "I_9") (pintype "input"))
    )
    (net (code "53") (name "/RES-LED-1") (class "Default")
      (node (ref "CON3-PCB1") (pin "1") (pinfunction "1_1") (pintype "passive"))
      (node (ref "L4") (pin "A") (pinfunction "A_A") (pintype "passive"))
    )
    (net (code "54") (name "/RES-LED-2") (class "Default")
      (node (ref "CON3-PCB2") (pin "1") (pinfunction "1_1") (pintype "passive"))
      (node (ref "IC3") (pin "12") (pinfunction "O_12") (pintype "output"))
    )
    (net (code "55") (name "/REV-1") (class "Default")
      (node (ref "CON1-PCB1") (pin "2") (pinfunction "2_2") (pintype "passive"))
      (node (ref "D7") (pin "ANODE") (pinfunction "A_ANODE") (pintype "passive"))
      (node (ref "R17") (pin "2") (pinfunction "2_2") (pintype "passive"))
    )
    (net (code "56") (name "/REV-2") (class "Default")
      (node (ref "CON1-PCB2") (pin "2") (pinfunction "2_2") (pintype "passive"))
      (node (ref "IC3") (pin "11") (pinfunction "I_11") (pintype "input"))
      (node (ref "IC3") (pin "5") (pinfunction "I_5") (pintype "input"))
    )
    (net (code "57") (name "/REV-LED-1") (class "Default")
      (node (ref "CON3-PCB1") (pin "2") (pinfunction "2_2") (pintype "passive"))
      (node (ref "IC1") (pin "13") (pinfunction "I1_13") (pintype "input"))
    )
    (net (code "58") (name "/REV-LED-2") (class "Default")
      (node (ref "CON3-PCB2") (pin "2") (pinfunction "2_2") (pintype "passive"))
      (node (ref "IC3") (pin "10") (pinfunction "O_10") (pintype "output"))
    )
    (net (code "59") (name "/STEP-LIMIT") (class "Default")
      (node (ref "Q1") (pin "1") (pinfunction "B_1") (pintype "passive"))
      (node (ref "SW2") (pin "2") (pinfunction "2_2") (pintype "passive"))
    )
    (net (code "60") (name "0V") (class "Default")
      (node (ref "C1") (pin "2") (pinfunction "2_2") (pintype "passive"))
      (node (ref "C10") (pin "2") (pinfunction "2_2") (pintype "passive"))
      (node (ref "C11") (pin "2") (pinfunction "2_2") (pintype "passive"))
      (node (ref "C12") (pin "1") (pinfunction "1_1") (pintype "passive"))
      (node (ref "C13") (pin "2") (pinfunction "2_2") (pintype "passive"))
      (node (ref "C14") (pin "1") (pinfunction "1_1") (pintype "passive"))
      (node (ref "C15") (pin "2") (pinfunction "2_2") (pintype "passive"))
      (node (ref "C16") (pin "1") (pinfunction "1_1") (pintype "passive"))
      (node (ref "C17") (pin "2") (pinfunction "2_2") (pintype "passive"))
      (node (ref "C18") (pin "2") (pinfunction "2_2") (pintype "passive"))
      (node (ref "C19") (pin "1") (pinfunction "1_1") (pintype "passive"))
      (node (ref "C2") (pin "1") (pinfunction "1_1") (pintype "passive"))
      (node (ref "C20") (pin "2") (pinfunction "2_2") (pintype "passive"))
      (node (ref "C21") (pin "2") (pinfunction "2_2") (pintype "passive"))
      (node (ref "C22") (pin "2") (pinfunction "2_2") (pintype "passive"))
      (node (ref "C23") (pin "2") (pinfunction "2_2") (pintype "passive"))
      (node (ref "C24") (pin "2") (pinfunction "2_2") (pintype "passive"))
      (node (ref "C25") (pin "2") (pinfunction "2_2") (pintype "passive"))
      (node (ref "C26") (pin "2") (pinfunction "2_2") (pintype "passive"))
      (node (ref "C27") (pin "1") (pinfunction "1_1") (pintype "passive"))
      (node (ref "C3") (pin "-") (pinfunction "-_-") (pintype "passive"))
      (node (ref "C4") (pin "+") (pinfunction "+_+") (pintype "passive"))
      (node (ref "C5") (pin "-") (pinfunction "-_-") (pintype "passive"))
      (node (ref "C6") (pin "2") (pinfunction "2_2") (pintype "passive"))
      (node (ref "C7") (pin "2") (pinfunction "2_2") (pintype "passive"))
      (node (ref "C8") (pin "2") (pinfunction "2_2") (pintype "passive"))
      (node (ref "C9") (pin "2") (pinfunction "2_2") (pintype "passive"))
      (node (ref "CON3-PCB1") (pin "6") (pinfunction "6_6") (pintype "passive"))
      (node (ref "CON3-PCB1") (pin "7") (pinfunction "7_7") (pintype "passive"))
      (node (ref "CON3-PCB2") (pin "6") (pinfunction "6_6") (pintype "passive"))
      (node (ref "CON3-PCB2") (pin "7") (pinfunction "7_7") (pintype "passive"))
      (node (ref "CON4-PCB2") (pin "10") (pinfunction "10_10") (pintype "passive"))
      (node (ref "CON4-PCB2") (pin "2") (pinfunction "2_2") (pintype "passive"))
      (node (ref "CON4-PCB3") (pin "10") (pinfunction "10_10") (pintype "passive"))
      (node (ref "CON4-PCB3") (pin "2") (pinfunction "2_2") (pintype "passive"))
      (node (ref "FWD") (pin "RING") (pinfunction "SLEEVE_RING") (pintype "bidirectional"))
      (node (ref "HLD") (pin "RING") (pinfunction "SLEEVE_RING") (pintype "bidirectional"))
      (node (ref "I/O1") (pin "RING") (pinfunction "SLEEVE_RING") (pintype "bidirectional"))
      (node (ref "I/O2") (pin "RING") (pinfunction "SLEEVE_RING") (pintype "bidirectional"))
      (node (ref "I/O3") (pin "RING") (pinfunction "SLEEVE_RING") (pintype "bidirectional"))
      (node (ref "I/O4") (pin "RING") (pinfunction "SLEEVE_RING") (pintype "bidirectional"))
      (node (ref "IC1") (pin "7") (pinfunction "VSS_7") (pintype "power_in"))
      (node (ref "IC10") (pin "11") (pinfunction "R2_11") (pintype "input"))
      (node (ref "IC10") (pin "12") (pinfunction "S2_12") (pintype "input"))
      (node (ref "IC10") (pin "14") (pinfunction "S3_14") (pintype "input"))
      (node (ref "IC10") (pin "15") (pinfunction "R3_15") (pintype "input"))
      (node (ref "IC10") (pin "8") (pinfunction "VSS_8") (pintype "power_in"))
      (node (ref "IC2") (pin "7") (pinfunction "VSS_7") (pintype "power_in"))
      (node (ref "IC3") (pin "7") (pinfunction "VSS_7") (pintype "power_in"))
      (node (ref "IC4") (pin "10") (pinfunction "+IN_10") (pintype "input"))
      (node (ref "IC4") (pin "3") (pinfunction "+IN_3") (pintype "input"))
      (node (ref "IC5") (pin "13") (pinfunction "P2_13") (pintype "input"))
      (node (ref "IC5") (pin "3") (pinfunction "P3_3") (pintype "input"))
      (node (ref "IC5") (pin "8") (pinfunction "VSS_8") (pintype "power_in"))
      (node (ref "IC6") (pin "15") (pinfunction "GND_15") (pintype "power_in"))
      (node (ref "IC7") (pin "15") (pinfunction "GND_15") (pintype "power_in"))
      (node (ref "IC8") (pin "12") (pinfunction "V-_12") (pintype "power_in"))
      (node (ref "IC9") (pin "3") (pinfunction "Y_3") (pintype "bidirectional"))
      (node (ref "IC9") (pin "6") (pinfunction "INH_6") (pintype "input"))
      (node (ref "IC9") (pin "7") (pinfunction "VEE_7") (pintype "power_in"))
      (node (ref "IC9") (pin "8") (pinfunction "GND_8") (pintype "power_in"))
      (node (ref "O/I1") (pin "RING") (pinfunction "SLEEVE_RING") (pintype "bidirectional"))
      (node (ref "O/I2") (pin "RING") (pinfunction "SLEEVE_RING") (pintype "bidirectional"))
      (node (ref "O/I3") (pin "RING") (pinfunction "SLEEVE_RING") (pintype "bidirectional"))
      (node (ref "O/I4") (pin "RING") (pinfunction "SLEEVE_RING") (pintype "bidirectional"))
      (node (ref "POWER") (pin "3") (pinfunction "3_3") (pintype "passive"))
      (node (ref "POWER") (pin "4") (pinfunction "4_4") (pintype "passive"))
      (node (ref "POWER") (pin "5") (pinfunction "5_5") (pintype "passive"))
      (node (ref "POWER") (pin "6") (pinfunction "6_6") (pintype "passive"))
      (node (ref "POWER") (pin "7") (pinfunction "7_7") (pintype "passive"))
      (node (ref "POWER") (pin "8") (pinfunction "8_8") (pintype "passive"))
      (node (ref "Q1") (pin "3") (pinfunction "E_3") (pintype "passive"))
      (node (ref "Q2") (pin "3") (pinfunction "E_3") (pintype "passive"))
      (node (ref "Q3") (pin "3") (pinfunction "E_3") (pintype "passive"))
      (node (ref "R10") (pin "2") (pinfunction "2_2") (pintype "passive"))
      (node (ref "R21") (pin "1") (pinfunction "1_1") (pintype "passive"))
      (node (ref "R23") (pin "1") (pinfunction "1_1") (pintype "passive"))
      (node (ref "R24") (pin "1") (pinfunction "1_1") (pintype "passive"))
      (node (ref "R25") (pin "1") (pinfunction "1_1") (pintype "passive"))
      (node (ref "R26") (pin "1") (pinfunction "1_1") (pintype "passive"))
      (node (ref "R3") (pin "2") (pinfunction "2_2") (pintype "passive"))
      (node (ref "R32") (pin "1") (pinfunction "1_1") (pintype "passive"))
      (node (ref "R4") (pin "2") (pinfunction "2_2") (pintype "passive"))
      (node (ref "R40") (pin "2") (pinfunction "2_2") (pintype "passive"))
      (node (ref "R47") (pin "2") (pinfunction "2_2") (pintype "passive"))
      (node (ref "R5") (pin "2") (pinfunction "2_2") (pintype "passive"))
      (node (ref "R55") (pin "2") (pinfunction "2_2") (pintype "passive"))
      (node (ref "R56") (pin "2") (pinfunction "2_2") (pintype "passive"))
      (node (ref "R57") (pin "2") (pinfunction "2_2") (pintype "passive"))
      (node (ref "R58") (pin "2") (pinfunction "2_2") (pintype "passive"))
      (node (ref "R59") (pin "1") (pinfunction "1_1") (pintype "passive"))
      (node (ref "R6") (pin "2") (pinfunction "2_2") (pintype "passive"))
      (node (ref "R7") (pin "2") (pinfunction "2_2") (pintype "passive"))
      (node (ref "RES") (pin "RING") (pinfunction "SLEEVE_RING") (pintype "bidirectional"))
      (node (ref "REV") (pin "RING") (pinfunction "SLEEVE_RING") (pintype "bidirectional"))
      (node (ref "RG1") (pin "2") (pinfunction "GND_2") (pintype "input"))
      (node (ref "SW1") (pin "3") (pinfunction "3_3") (pintype "passive"))
      (node (ref "SW3") (pin "P$1") (pinfunction "1_P$1") (pintype "bidirectional"))
      (node (ref "SW3") (pin "P$2") (pinfunction "2_P$2") (pintype "bidirectional"))
      (node (ref "SW4") (pin "P$1") (pinfunction "1_P$1") (pintype "bidirectional"))
      (node (ref "SW4") (pin "P$2") (pinfunction "2_P$2") (pintype "bidirectional"))
      (node (ref "SW5") (pin "P$1") (pinfunction "1_P$1") (pintype "bidirectional"))
      (node (ref "SW5") (pin "P$2") (pinfunction "2_P$2") (pintype "bidirectional"))
      (node (ref "SW6") (pin "P$1") (pinfunction "1_P$1") (pintype "bidirectional"))
      (node (ref "SW6") (pin "P$2") (pinfunction "2_P$2") (pintype "bidirectional"))
    )
    (net (code "61") (name "Net-(D1-PadA)") (class "Default")
      (node (ref "D1") (pin "A") (pinfunction "A_A") (pintype "passive"))
      (node (ref "R1") (pin "2") (pinfunction "2_2") (pintype "passive"))
    )
    (net (code "62") (name "Net-(D2-PadC)") (class "Default")
      (node (ref "D2") (pin "C") (pinfunction "C_C") (pintype "passive"))
      (node (ref "R2") (pin "2") (pinfunction "2_2") (pintype "passive"))
    )
    (net (code "63") (name "Net-(D3-A)") (class "Default")
      (node (ref "D3") (pin "ANODE") (pinfunction "A_ANODE") (pintype "passive"))
      (node (ref "IC1") (pin "3") (pinfunction "O_3") (pintype "output"))
    )
    (net (code "64") (name "Net-(D3-C)") (class "Default")
      (node (ref "D3") (pin "CATHODE") (pinfunction "C_CATHODE") (pintype "passive"))
      (node (ref "D4") (pin "CATHODE") (pinfunction "C_CATHODE") (pintype "passive"))
      (node (ref "R55") (pin "1") (pinfunction "1_1") (pintype "passive"))
      (node (ref "SW2") (pin "3") (pinfunction "3_3") (pintype "passive"))
    )
    (net (code "65") (name "Net-(D4-A)") (class "Default")
      (node (ref "D4") (pin "ANODE") (pinfunction "A_ANODE") (pintype "passive"))
      (node (ref "IC1") (pin "4") (pinfunction "O_4") (pintype "output"))
    )
    (net (code "66") (name "Net-(D5-C)") (class "Default")
      (node (ref "C7") (pin "1") (pinfunction "1_1") (pintype "passive"))
      (node (ref "D5") (pin "CATHODE") (pinfunction "C_CATHODE") (pintype "passive"))
      (node (ref "SW3") (pin "P$3") (pinfunction "3_P$3") (pintype "bidirectional"))
      (node (ref "SW3") (pin "P$4") (pinfunction "4_P$4") (pintype "bidirectional"))
    )
    (net (code "67") (name "Net-(D6-C)") (class "Default")
      (node (ref "C8") (pin "1") (pinfunction "1_1") (pintype "passive"))
      (node (ref "D6") (pin "CATHODE") (pinfunction "C_CATHODE") (pintype "passive"))
      (node (ref "SW4") (pin "P$3") (pinfunction "3_P$3") (pintype "bidirectional"))
      (node (ref "SW4") (pin "P$4") (pinfunction "4_P$4") (pintype "bidirectional"))
    )
    (net (code "68") (name "Net-(D7-C)") (class "Default")
      (node (ref "C9") (pin "1") (pinfunction "1_1") (pintype "passive"))
      (node (ref "D7") (pin "CATHODE") (pinfunction "C_CATHODE") (pintype "passive"))
      (node (ref "SW5") (pin "P$3") (pinfunction "3_P$3") (pintype "bidirectional"))
      (node (ref "SW5") (pin "P$4") (pinfunction "4_P$4") (pintype "bidirectional"))
    )
    (net (code "69") (name "Net-(D8-C)") (class "Default")
      (node (ref "C10") (pin "1") (pinfunction "1_1") (pintype "passive"))
      (node (ref "D8") (pin "CATHODE") (pinfunction "C_CATHODE") (pintype "passive"))
      (node (ref "SW6") (pin "P$3") (pinfunction "3_P$3") (pintype "bidirectional"))
      (node (ref "SW6") (pin "P$4") (pinfunction "4_P$4") (pintype "bidirectional"))
    )
    (net (code "70") (name "Net-(D9-A)") (class "Default")
      (node (ref "D9") (pin "ANODE") (pinfunction "A_ANODE") (pintype "passive"))
      (node (ref "IC3") (pin "6") (pinfunction "O_6") (pintype "output"))
    )
    (net (code "71") (name "Net-(D10-A)") (class "Default")
      (node (ref "D10") (pin "ANODE") (pinfunction "A_ANODE") (pintype "passive"))
      (node (ref "IC3") (pin "4") (pinfunction "O_4") (pintype "output"))
      (node (ref "IC5") (pin "10") (pinfunction "U/~{D}_10") (pintype "input"))
    )
    (net (code "72") (name "Net-(D10-C)") (class "Default")
      (node (ref "D10") (pin "CATHODE") (pinfunction "C_CATHODE") (pintype "passive"))
      (node (ref "D9") (pin "CATHODE") (pinfunction "C_CATHODE") (pintype "passive"))
      (node (ref "R21") (pin "2") (pinfunction "2_2") (pintype "passive"))
      (node (ref "R22") (pin "2") (pinfunction "2_2") (pintype "passive"))
    )
    (net (code "73") (name "Net-(D11-A)") (class "Default")
      (node (ref "D11") (pin "ANODE") (pinfunction "A_ANODE") (pintype "passive"))
      (node (ref "IC4") (pin "6") (pinfunction "-IN_6") (pintype "input"))
      (node (ref "R27") (pin "1") (pinfunction "1_1") (pintype "passive"))
    )
    (net (code "74") (name "Net-(D11-C)") (class "Default")
      (node (ref "D11") (pin "CATHODE") (pinfunction "C_CATHODE") (pintype "passive"))
      (node (ref "IC4") (pin "7") (pinfunction "OUT_7") (pintype "output"))
    )
    (net (code "75") (name "Net-(D12-A)") (class "Default")
      (node (ref "D12") (pin "ANODE") (pinfunction "A_ANODE") (pintype "passive"))
      (node (ref "R20") (pin "2") (pinfunction "2_2") (pintype "passive"))
      (node (ref "R52") (pin "1") (pinfunction "1_1") (pintype "passive"))
    )
    (net (code "76") (name "Net-(D12-C)") (class "Default")
      (node (ref "D12") (pin "CATHODE") (pinfunction "C_CATHODE") (pintype "passive"))
      (node (ref "IC4") (pin "1") (pinfunction "OUT_1") (pintype "output"))
    )
    (net (code "77") (name "Net-(D13-A)") (class "Default")
      (node (ref "D13") (pin "ANODE") (pinfunction "A_ANODE") (pintype "passive"))
      (node (ref "IC8") (pin "2") (pinfunction "OUT_2") (pintype "output"))
      (node (ref "R41") (pin "2") (pinfunction "2_2") (pintype "passive"))
      (node (ref "R44") (pin "1") (pinfunction "1_1") (pintype "passive"))
    )
    (net (code "78") (name "Net-(D14-A)") (class "Default")
      (node (ref "D14") (pin "ANODE") (pinfunction "A_ANODE") (pintype "passive"))
      (node (ref "IC8") (pin "13") (pinfunction "OUT_13") (pintype "output"))
      (node (ref "IC8") (pin "14") (pinfunction "OUT_14") (pintype "output"))
      (node (ref "R43") (pin "2") (pinfunction "2_2") (pintype "passive"))
      (node (ref "R46") (pin "1") (pinfunction "1_1") (pintype "passive"))
    )
    (net (code "79") (name "Net-(HLD-PadTIP)") (class "Default")
      (node (ref "HLD") (pin "TIP") (pinfunction "TIP_TIP") (pintype "bidirectional"))
      (node (ref "R11") (pin "1") (pinfunction "1_1") (pintype "passive"))
      (node (ref "R7") (pin "1") (pinfunction "1_1") (pintype "passive"))
    )
    (net (code "80") (name "Net-(IC2A-I)") (class "Default")
      (node (ref "IC2") (pin "1") (pinfunction "I_1") (pintype "input"))
      (node (ref "R11") (pin "2") (pinfunction "2_2") (pintype "passive"))
    )
    (net (code "81") (name "Net-(IC2A-O)") (class "Default")
      (node (ref "IC2") (pin "2") (pinfunction "O_2") (pintype "output"))
      (node (ref "R15") (pin "1") (pinfunction "1_1") (pintype "passive"))
    )
    (net (code "82") (name "Net-(IC2B-I)") (class "Default")
      (node (ref "IC2") (pin "3") (pinfunction "I_3") (pintype "input"))
      (node (ref "R12") (pin "2") (pinfunction "2_2") (pintype "passive"))
    )
    (net (code "83") (name "Net-(IC2B-O)") (class "Default")
      (node (ref "IC2") (pin "4") (pinfunction "O_4") (pintype "output"))
      (node (ref "R16") (pin "1") (pinfunction "1_1") (pintype "passive"))
    )
    (net (code "84") (name "Net-(IC2C-I)") (class "Default")
      (node (ref "IC2") (pin "5") (pinfunction "I_5") (pintype "input"))
      (node (ref "R13") (pin "2") (pinfunction "2_2") (pintype "passive"))
    )
    (net (code "85") (name "Net-(IC2C-O)") (class "Default")
      (node (ref "IC2") (pin "6") (pinfunction "O_6") (pintype "output"))
      (node (ref "R17") (pin "1") (pinfunction "1_1") (pintype "passive"))
    )
    (net (code "86") (name "Net-(IC2D-I)") (class "Default")
      (node (ref "IC2") (pin "9") (pinfunction "I_9") (pintype "input"))
      (node (ref "R14") (pin "2") (pinfunction "2_2") (pintype "passive"))
    )
    (net (code "87") (name "Net-(IC2D-O)") (class "Default")
      (node (ref "IC2") (pin "8") (pinfunction "O_8") (pintype "output"))
      (node (ref "R18") (pin "1") (pinfunction "1_1") (pintype "passive"))
    )
    (net (code "88") (name "Net-(IC2E-O)") (class "Default")
      (node (ref "IC2") (pin "10") (pinfunction "O_10") (pintype "output"))
      (node (ref "L1") (pin "A") (pinfunction "A_A") (pintype "passive"))
    )
    (net (code "89") (name "Net-(IC3A-O)") (class "Default")
      (node (ref "IC3") (pin "2") (pinfunction "O_2") (pintype "output"))
      (node (ref "IC5") (pin "5") (pinfunction "CIN_5") (pintype "input"))
    )
    (net (code "90") (name "Net-(IC3D-O)") (class "Default")
      (node (ref "IC3") (pin "8") (pinfunction "O_8") (pintype "output"))
      (node (ref "IC5") (pin "9") (pinfunction "RES_9") (pintype "input"))
    )
    (net (code "91") (name "Net-(IC4A--IN)") (class "Default")
      (node (ref "IC4") (pin "2") (pinfunction "-IN_2") (pintype "input"))
      (node (ref "R20") (pin "1") (pinfunction "1_1") (pintype "passive"))
      (node (ref "R8") (pin "1") (pinfunction "1_1") (pintype "passive"))
      (node (ref "R9") (pin "1") (pinfunction "1_1") (pintype "passive"))
    )
    (net (code "92") (name "Net-(IC4B-+IN)") (class "Default")
      (node (ref "IC4") (pin "12") (pinfunction "+IN_12") (pintype "input"))
      (node (ref "IC4") (pin "5") (pinfunction "+IN_5") (pintype "input"))
      (node (ref "R19") (pin "2") (pinfunction "2_2") (pintype "passive"))
    )
    (net (code "93") (name "Net-(IC4C--IN)") (class "Default")
      (node (ref "IC4") (pin "9") (pinfunction "-IN_9") (pintype "input"))
      (node (ref "R27") (pin "2") (pinfunction "2_2") (pintype "passive"))
      (node (ref "R28") (pin "1") (pinfunction "1_1") (pintype "passive"))
      (node (ref "R52") (pin "2") (pinfunction "2_2") (pintype "passive"))
    )
    (net (code "94") (name "Net-(IC4C-OUT)") (class "Default")
      (node (ref "IC4") (pin "8") (pinfunction "OUT_8") (pintype "output"))
      (node (ref "R28") (pin "2") (pinfunction "2_2") (pintype "passive"))
      (node (ref "R29") (pin "1") (pinfunction "1_1") (pintype "passive"))
      (node (ref "R30") (pin "1") (pinfunction "1_1") (pintype "passive"))
      (node (ref "R31") (pin "1") (pinfunction "1_1") (pintype "passive"))
    )
    (net (code "95") (name "Net-(IC4D--IN)") (class "Default")
      (node (ref "IC4") (pin "13") (pinfunction "-IN_13") (pintype "input"))
      (node (ref "IC4") (pin "14") (pinfunction "OUT_14") (pintype "output"))
      (node (ref "R8") (pin "2") (pinfunction "2_2") (pintype "passive"))
    )
    (net (code "96") (name "Net-(IC5A-CLK)") (class "Default")
      (node (ref "C11") (pin "1") (pinfunction "1_1") (pintype "passive"))
      (node (ref "IC5") (pin "15") (pinfunction "CLK_15") (pintype "input"))
      (node (ref "R22") (pin "1") (pinfunction "1_1") (pintype "passive"))
    )
    (net (code "97") (name "Net-(IC5A-Q0)") (class "Default")
      (node (ref "IC5") (pin "6") (pinfunction "Q0_6") (pintype "output"))
      (node (ref "IC6") (pin "1") (pinfunction "A0_1") (pintype "input"))
      (node (ref "IC7") (pin "1") (pinfunction "A0_1") (pintype "input"))
      (node (ref "IC9") (pin "10") (pinfunction "A_10") (pintype "input"))
    )
    (net (code "98") (name "Net-(IC5A-Q1)") (class "Default")
      (node (ref "IC5") (pin "11") (pinfunction "Q1_11") (pintype "output"))
      (node (ref "IC6") (pin "16") (pinfunction "A1_16") (pintype "input"))
      (node (ref "IC7") (pin "16") (pinfunction "A1_16") (pintype "input"))
      (node (ref "IC9") (pin "9") (pinfunction "B_9") (pintype "input"))
    )
    (net (code "99") (name "Net-(IC6-DA)") (class "Default")
      (node (ref "IC6") (pin "8") (pinfunction "DA_8") (pintype "passive"))
      (node (ref "R33") (pin "1") (pinfunction "1_1") (pintype "passive"))
    )
    (net (code "100") (name "Net-(IC6-DB)") (class "Default")
      (node (ref "IC6") (pin "9") (pinfunction "DB_9") (pintype "passive"))
      (node (ref "R34") (pin "1") (pinfunction "1_1") (pintype "passive"))
    )
    (net (code "101") (name "Net-(IC6-S1A)") (class "Default")
      (node (ref "IC6") (pin "10") (pinfunction "S4B_10") (pintype "passive"))
      (node (ref "IC6") (pin "4") (pinfunction "S1A_4") (pintype "passive"))
      (node (ref "IC7") (pin "12") (pinfunction "S2B_12") (pintype "passive"))
      (node (ref "IC7") (pin "6") (pinfunction "S3A_6") (pintype "passive"))
      (node (ref "R23") (pin "2") (pinfunction "2_2") (pintype "passive"))
      (node (ref "R48") (pin "2") (pinfunction "2_2") (pintype "passive"))
    )
    (net (code "102") (name "Net-(IC6-S1B)") (class "Default")
      (node (ref "IC6") (pin "13") (pinfunction "S1B_13") (pintype "passive"))
      (node (ref "IC6") (pin "5") (pinfunction "S2A_5") (pintype "passive"))
      (node (ref "IC7") (pin "11") (pinfunction "S3B_11") (pintype "passive"))
      (node (ref "IC7") (pin "7") (pinfunction "S4A_7") (pintype "passive"))
      (node (ref "R24") (pin "2") (pinfunction "2_2") (pintype "passive"))
      (node (ref "R49") (pin "2") (pinfunction "2_2") (pintype "passive"))
    )
    (net (code "103") (name "Net-(IC6-S2B)") (class "Default")
      (node (ref "IC6") (pin "12") (pinfunction "S2B_12") (pintype "passive"))
      (node (ref "IC6") (pin "6") (pinfunction "S3A_6") (pintype "passive"))
      (node (ref "IC7") (pin "10") (pinfunction "S4B_10") (pintype "passive"))
      (node (ref "IC7") (pin "4") (pinfunction "S1A_4") (pintype "passive"))
      (node (ref "R25") (pin "2") (pinfunction "2_2") (pintype "passive"))
      (node (ref "R50") (pin "2") (pinfunction "2_2") (pintype "passive"))
    )
    (net (code "104") (name "Net-(IC6-S3B)") (class "Default")
      (node (ref "IC6") (pin "11") (pinfunction "S3B_11") (pintype "passive"))
      (node (ref "IC6") (pin "7") (pinfunction "S4A_7") (pintype "passive"))
      (node (ref "IC7") (pin "13") (pinfunction "S1B_13") (pintype "passive"))
      (node (ref "IC7") (pin "5") (pinfunction "S2A_5") (pintype "passive"))
      (node (ref "R26") (pin "2") (pinfunction "2_2") (pintype "passive"))
      (node (ref "R51") (pin "2") (pinfunction "2_2") (pintype "passive"))
    )
    (net (code "105") (name "Net-(IC7-DA)") (class "Default")
      (node (ref "IC7") (pin "8") (pinfunction "DA_8") (pintype "passive"))
      (node (ref "R35") (pin "1") (pinfunction "1_1") (pintype "passive"))
    )
    (net (code "106") (name "Net-(IC7-DB)") (class "Default")
      (node (ref "IC7") (pin "9") (pinfunction "DB_9") (pintype "passive"))
      (node (ref "R36") (pin "1") (pinfunction "1_1") (pintype "passive"))
    )
    (net (code "107") (name "Net-(IC8A-+IN)") (class "Default")
      (node (ref "IC8") (pin "5") (pinfunction "+IN_5") (pintype "input"))
      (node (ref "R29") (pin "2") (pinfunction "2_2") (pintype "passive"))
      (node (ref "R41") (pin "1") (pinfunction "1_1") (pintype "passive"))
    )
    (net (code "108") (name "Net-(IC8A--IN)") (class "Default")
      (node (ref "IC8") (pin "4") (pinfunction "-IN_4") (pintype "input"))
      (node (ref "R37") (pin "2") (pinfunction "2_2") (pintype "passive"))
      (node (ref "R38") (pin "1") (pinfunction "1_1") (pintype "passive"))
    )
    (net (code "109") (name "Net-(IC8B-+IN)") (class "Default")
      (node (ref "IC8") (pin "7") (pinfunction "+IN_7") (pintype "input"))
      (node (ref "R30") (pin "2") (pinfunction "2_2") (pintype "passive"))
      (node (ref "R42") (pin "1") (pinfunction "1_1") (pintype "passive"))
    )
    (net (code "110") (name "Net-(IC8B--IN)") (class "Default")
      (node (ref "IC8") (pin "6") (pinfunction "-IN_6") (pintype "input"))
      (node (ref "R38") (pin "2") (pinfunction "2_2") (pintype "passive"))
      (node (ref "R39") (pin "1") (pinfunction "1_1") (pintype "passive"))
    )
    (net (code "111") (name "Net-(IC8C-+IN)") (class "Default")
      (node (ref "IC8") (pin "9") (pinfunction "+IN_9") (pintype "input"))
      (node (ref "R31") (pin "2") (pinfunction "2_2") (pintype "passive"))
      (node (ref "R43") (pin "1") (pinfunction "1_1") (pintype "passive"))
    )
    (net (code "112") (name "Net-(IC8C--IN)") (class "Default")
      (node (ref "IC8") (pin "11") (pinfunction "+IN_11") (pintype "input"))
      (node (ref "IC8") (pin "8") (pinfunction "-IN_8") (pintype "input"))
      (node (ref "R39") (pin "2") (pinfunction "2_2") (pintype "passive"))
      (node (ref "R40") (pin "1") (pinfunction "1_1") (pintype "passive"))
    )
    (net (code "113") (name "Net-(L1-C)") (class "Default")
      (node (ref "L1") (pin "K") (pinfunction "C_K") (pintype "passive"))
      (node (ref "R3") (pin "1") (pinfunction "1_1") (pintype "passive"))
    )
    (net (code "114") (name "Net-(L2-C)") (class "Default")
      (node (ref "L2") (pin "K") (pinfunction "C_K") (pintype "passive"))
      (node (ref "R4") (pin "1") (pinfunction "1_1") (pintype "passive"))
    )
    (net (code "115") (name "Net-(L3-C)") (class "Default")
      (node (ref "L3") (pin "K") (pinfunction "C_K") (pintype "passive"))
      (node (ref "R5") (pin "1") (pinfunction "1_1") (pintype "passive"))
    )
    (net (code "116") (name "Net-(L4-C)") (class "Default")
      (node (ref "L4") (pin "K") (pinfunction "C_K") (pintype "passive"))
      (node (ref "R6") (pin "1") (pinfunction "1_1") (pintype "passive"))
    )
    (net (code "117") (name "Net-(L5-C)") (class "Default")
      (node (ref "L5") (pin "K") (pinfunction "C_K") (pintype "passive"))
      (node (ref "L6") (pin "K") (pinfunction "C_K") (pintype "passive"))
      (node (ref "L7") (pin "K") (pinfunction "C_K") (pintype "passive"))
      (node (ref "L8") (pin "K") (pinfunction "C_K") (pintype "passive"))
      (node (ref "R32") (pin "2") (pinfunction "2_2") (pintype "passive"))
    )
    (net (code "118") (name "Net-(POWER-Pad1)") (class "Default")
      (node (ref "POWER") (pin "1") (pinfunction "1_1") (pintype "passive"))
      (node (ref "POWER") (pin "2") (pinfunction "2_2") (pintype "passive"))
      (node (ref "R2") (pin "1") (pinfunction "1_1") (pintype "passive"))
    )
    (net (code "119") (name "Net-(POWER-Pad10)") (class "Default")
      (node (ref "POWER") (pin "10") (pinfunction "10_10") (pintype "passive"))
      (node (ref "POWER") (pin "9") (pinfunction "9_9") (pintype "passive"))
      (node (ref "R1") (pin "1") (pinfunction "1_1") (pintype "passive"))
    )
    (net (code "120") (name "Net-(Q3-C)") (class "Default")
      (node (ref "Q3") (pin "2") (pinfunction "C_2") (pintype "passive"))
      (node (ref "R54") (pin "1") (pinfunction "1_1") (pintype "passive"))
      (node (ref "SW2") (pin "1") (pinfunction "1_1") (pintype "passive"))
    )
    (net (code "121") (name "Net-(R10-Pad1)") (class "Default")
      (node (ref "R10") (pin "1") (pinfunction "1_1") (pintype "passive"))
      (node (ref "R14") (pin "1") (pinfunction "1_1") (pintype "passive"))
      (node (ref "RES") (pin "TIP") (pinfunction "TIP_TIP") (pintype "bidirectional"))
    )
    (net (code "122") (name "unconnected-(FWD-SHUNT-PadNORMAL)") (class "Default")
      (node (ref "FWD") (pin "NORMAL") (pinfunction "SHUNT_NORMAL") (pintype "bidirectional"))
    )
    (net (code "123") (name "unconnected-(HLD-SHUNT-PadNORMAL)") (class "Default")
      (node (ref "HLD") (pin "NORMAL") (pinfunction "SHUNT_NORMAL") (pintype "bidirectional"))
    )
    (net (code "124") (name "unconnected-(I/O1-SHUNT-PadNORMAL)") (class "Default")
      (node (ref "I/O1") (pin "NORMAL") (pinfunction "SHUNT_NORMAL") (pintype "bidirectional"))
    )
    (net (code "125") (name "unconnected-(I/O2-SHUNT-PadNORMAL)") (class "Default")
      (node (ref "I/O2") (pin "NORMAL") (pinfunction "SHUNT_NORMAL") (pintype "bidirectional"))
    )
    (net (code "126") (name "unconnected-(I/O3-SHUNT-PadNORMAL)") (class "Default")
      (node (ref "I/O3") (pin "NORMAL") (pinfunction "SHUNT_NORMAL") (pintype "bidirectional"))
    )
    (net (code "127") (name "unconnected-(I/O4-SHUNT-PadNORMAL)") (class "Default")
      (node (ref "I/O4") (pin "NORMAL") (pinfunction "SHUNT_NORMAL") (pintype "bidirectional"))
    )
    (net (code "128") (name "unconnected-(IC5A-CO-Pad7)") (class "Default")
      (node (ref "IC5") (pin "7") (pinfunction "CO_7") (pintype "output"))
    )
    (net (code "129") (name "unconnected-(IC5A-Q2-Pad14)") (class "Default")
      (node (ref "IC5") (pin "14") (pinfunction "Q2_14") (pintype "output"))
    )
    (net (code "130") (name "unconnected-(IC5A-Q3-Pad2)") (class "Default")
      (node (ref "IC5") (pin "2") (pinfunction "Q3_2") (pintype "output"))
    )
    (net (code "131") (name "unconnected-(IC9A-Y0-Pad1)") (class "Default")
      (node (ref "IC9") (pin "1") (pinfunction "Y0_1") (pintype "bidirectional"))
    )
    (net (code "132") (name "unconnected-(IC9A-Y1-Pad5)") (class "Default")
      (node (ref "IC9") (pin "5") (pinfunction "Y1_5") (pintype "bidirectional"))
    )
    (net (code "133") (name "unconnected-(IC9A-Y2-Pad2)") (class "Default")
      (node (ref "IC9") (pin "2") (pinfunction "Y2_2") (pintype "bidirectional"))
    )
    (net (code "134") (name "unconnected-(IC9A-Y3-Pad4)") (class "Default")
      (node (ref "IC9") (pin "4") (pinfunction "Y3_4") (pintype "bidirectional"))
    )
    (net (code "135") (name "unconnected-(IC10A-Q2-Pad10)") (class "Default")
      (node (ref "IC10") (pin "10") (pinfunction "Q2_10") (pintype "output"))
    )
    (net (code "136") (name "unconnected-(IC10A-Q3-Pad1)") (class "Default")
      (node (ref "IC10") (pin "1") (pinfunction "Q3_1") (pintype "output"))
    )
    (net (code "137") (name "unconnected-(O/I1-SHUNT-PadNORMAL)") (class "Default")
      (node (ref "O/I1") (pin "NORMAL") (pinfunction "SHUNT_NORMAL") (pintype "bidirectional"))
    )
    (net (code "138") (name "unconnected-(O/I2-SHUNT-PadNORMAL)") (class "Default")
      (node (ref "O/I2") (pin "NORMAL") (pinfunction "SHUNT_NORMAL") (pintype "bidirectional"))
    )
    (net (code "139") (name "unconnected-(O/I3-SHUNT-PadNORMAL)") (class "Default")
      (node (ref "O/I3") (pin "NORMAL") (pinfunction "SHUNT_NORMAL") (pintype "bidirectional"))
    )
    (net (code "140") (name "unconnected-(O/I4-SHUNT-PadNORMAL)") (class "Default")
      (node (ref "O/I4") (pin "NORMAL") (pinfunction "SHUNT_NORMAL") (pintype "bidirectional"))
    )
    (net (code "141") (name "unconnected-(RES-SHUNT-PadNORMAL)") (class "Default")
      (node (ref "RES") (pin "NORMAL") (pinfunction "SHUNT_NORMAL") (pintype "bidirectional"))
    )
    (net (code "142") (name "unconnected-(REV-SHUNT-PadNORMAL)") (class "Default")
      (node (ref "REV") (pin "NORMAL") (pinfunction "SHUNT_NORMAL") (pintype "bidirectional"))
    )
  )
)
